# MCU_Design_exp.net
KiCad netlist of a schematic drawn in EAGLE
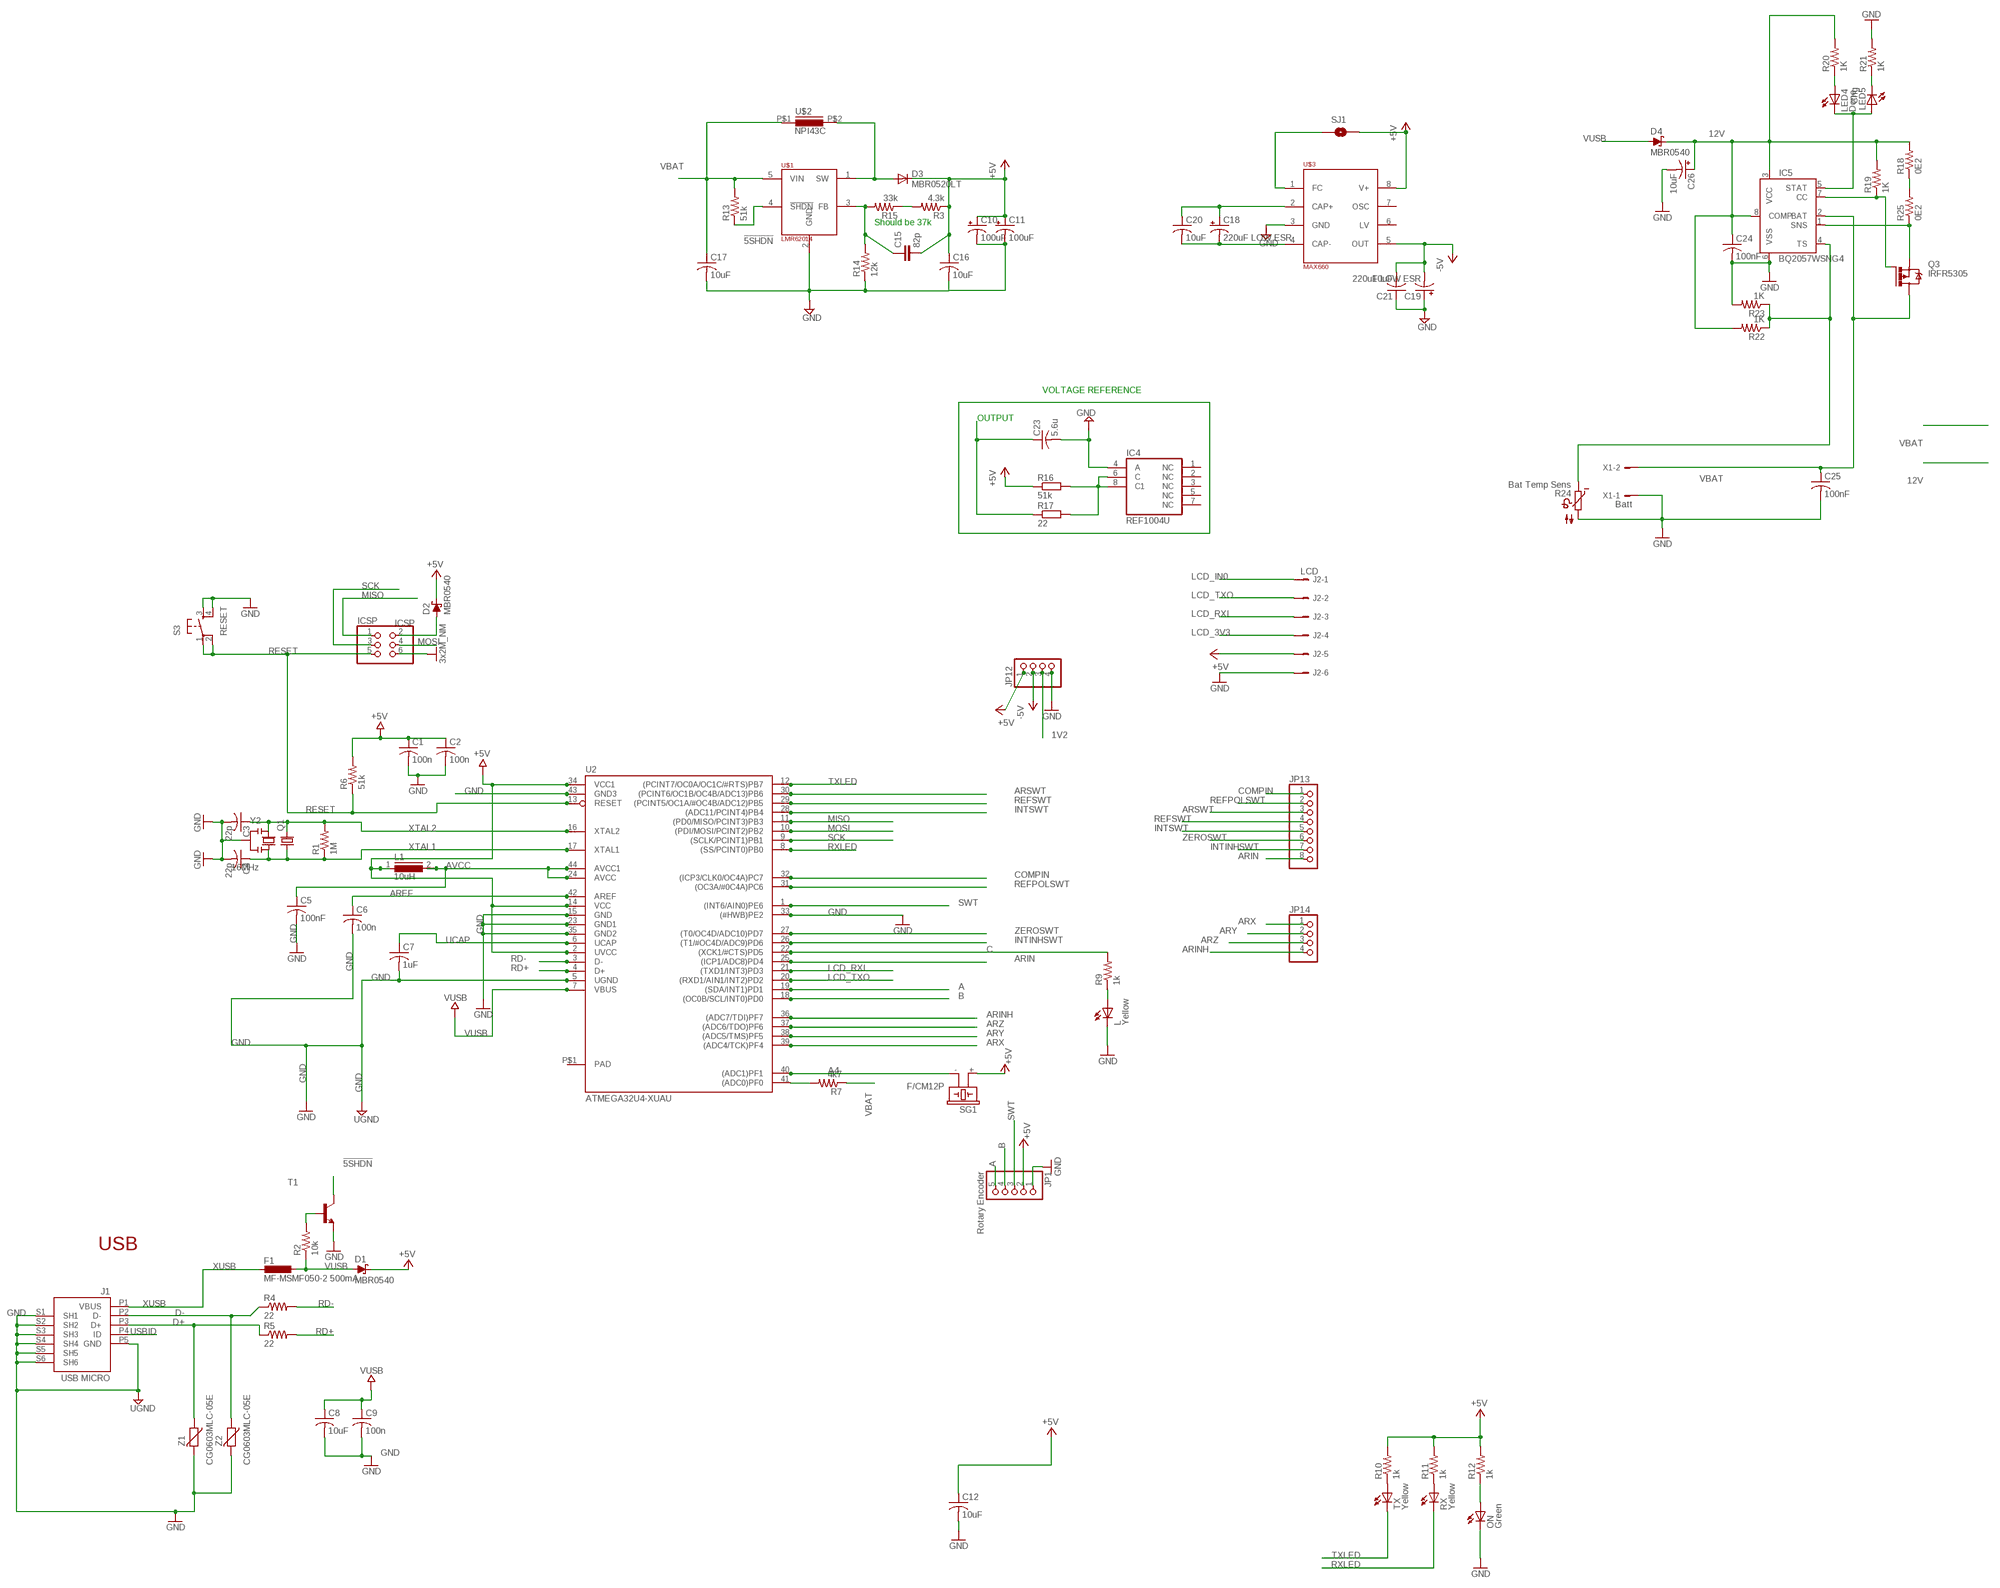
[diagram p0: schematic, sheet 1]

(export (version "E")
  (design (tool "Eeschema 10.0.6"))
  (components
    (comp (ref "C1")
      (value "100n")
      (footprint "eagle-import:C0805")
      (libsource (lib "eagle-import") (part "resistor_C-USC0805"))
    )
    (comp (ref "C2")
      (value "100n")
      (footprint "eagle-import:C0805")
      (libsource (lib "eagle-import") (part "resistor_C-USC0805"))
    )
    (comp (ref "C3")
      (value "22p")
      (footprint "eagle-import:C0805")
      (libsource (lib "eagle-import") (part "resistor_C-USC0805"))
    )
    (comp (ref "C4")
      (value "22p")
      (footprint "eagle-import:C0805")
      (libsource (lib "eagle-import") (part "resistor_C-USC0805"))
    )
    (comp (ref "C5")
      (value "100nF")
      (footprint "eagle-import:C0805")
      (libsource (lib "eagle-import") (part "resistor_C-USC0805"))
    )
    (comp (ref "C6")
      (value "100n")
      (footprint "eagle-import:C0805")
      (libsource (lib "eagle-import") (part "resistor_C-USC0805"))
    )
    (comp (ref "C7")
      (value "1uF")
      (footprint "eagle-import:C0805")
      (libsource (lib "eagle-import") (part "resistor_C-USC0805"))
    )
    (comp (ref "C8")
      (value "10uF")
      (footprint "eagle-import:C0805")
      (libsource (lib "eagle-import") (part "resistor_C-USC0805"))
    )
    (comp (ref "C9")
      (value "100n")
      (footprint "eagle-import:C0805")
      (libsource (lib "eagle-import") (part "resistor_C-USC0805"))
    )
    (comp (ref "C10")
      (value "100uF")
      (footprint "eagle-import:PANASONIC_D")
      (libsource (lib "eagle-import") (part "CPOL-USD"))
    )
    (comp (ref "C11")
      (value "100uF")
      (footprint "eagle-import:PANASONIC_D")
      (libsource (lib "eagle-import") (part "CPOL-USD"))
    )
    (comp (ref "C12")
      (value "10uF")
      (footprint "eagle-import:C0805")
      (libsource (lib "eagle-import") (part "resistor_C-USC0805"))
    )
    (comp (ref "C15")
      (value "82p")
      (footprint "eagle-import:C0805")
      (libsource (lib "eagle-import") (part "C-EUC0805"))
    )
    (comp (ref "C16")
      (value "10uF")
      (footprint "eagle-import:C0805")
      (libsource (lib "eagle-import") (part "resistor_C-USC0805"))
    )
    (comp (ref "C17")
      (value "10uF")
      (footprint "eagle-import:C0805")
      (libsource (lib "eagle-import") (part "resistor_C-USC0805"))
    )
    (comp (ref "C18")
      (value "220uF LOW ESR")
      (footprint "eagle-import:PANASONIC_D")
      (libsource (lib "eagle-import") (part "CPOL-USD"))
    )
    (comp (ref "C19")
      (value "220uF LOW ESR")
      (footprint "eagle-import:PANASONIC_D")
      (libsource (lib "eagle-import") (part "CPOL-USD"))
    )
    (comp (ref "C20")
      (value "10uF")
      (footprint "eagle-import:C0805")
      (libsource (lib "eagle-import") (part "resistor_C-USC0805"))
    )
    (comp (ref "C21")
      (value "10uF")
      (footprint "eagle-import:C0805")
      (libsource (lib "eagle-import") (part "resistor_C-USC0805"))
    )
    (comp (ref "C23")
      (value "5.6u")
      (footprint "eagle-import:C0805K")
      (libsource (lib "eagle-import") (part "C-USC0805K"))
    )
    (comp (ref "C24")
      (value "100nF")
      (footprint "eagle-import:C0805K")
      (libsource (lib "eagle-import") (part "resistor_C-USC0805K"))
    )
    (comp (ref "C25")
      (value "100nF")
      (footprint "eagle-import:C0805K")
      (libsource (lib "eagle-import") (part "resistor_C-USC0805K"))
    )
    (comp (ref "C26")
      (value "10uF")
      (footprint "eagle-import:153CLV-0405")
      (libsource (lib "eagle-import") (part "CPOL-US153CLV-0405"))
    )
    (comp (ref "D1")
      (value "MBR0540")
      (footprint "eagle-import:SOD123@2")
      (libsource (lib "eagle-import") (part "MBR0540"))
    )
    (comp (ref "D2")
      (value "MBR0540")
      (footprint "eagle-import:SOD123@2")
      (libsource (lib "eagle-import") (part "MBR0540"))
    )
    (comp (ref "D3")
      (value "MBR0520LT")
      (footprint "eagle-import:SOD123")
      (libsource (lib "eagle-import") (part "MBR0520LT"))
    )
    (comp (ref "D4")
      (value "MBR0540")
      (footprint "eagle-import:SOD123@2")
      (libsource (lib "eagle-import") (part "MBR0540"))
    )
    (comp (ref "F1")
      (value "MF-MSMF050-2 500mA")
      (footprint "eagle-import:L1812")
      (libsource (lib "eagle-import") (part "L-EUL1812"))
    )
    (comp (ref "IC4")
      (value "REF1004U")
      (footprint "eagle-import:SO08")
      (fields (field (name "MF") "TEXAS INSTRUMENTS") (field (name "MPN") "REF1004C-1.2"))
      (libsource (lib "eagle-import") (part "REF1004U"))
    )
    (comp (ref "IC5")
      (value "BQ2057WSNG4")
      (footprint "eagle-import:D_R-PDSO-G8")
      (libsource (lib "eagle-import") (part "BQ2057WSNG4"))
    )
    (comp (ref "ICSP")
      (value "ICSP")
      (footprint "eagle-import:2X03")
      (libsource (lib "eagle-import") (part "PINHD-2X3"))
    )
    (comp (ref "J1")
      (value "USB MICRO")
      (footprint "eagle-import:CON2_USB_MICRO_B_AT")
      (libsource (lib "eagle-import") (part "MYCON2_USB-MINI-B"))
    )
    (comp (ref "J2")
      (value "LCD")
      (footprint "eagle-import:7395-06")
      (libsource (lib "eagle-import") (part "22-?-0605-7068"))
    )
    (comp (ref "JP1")
      (value "Rotary Encoder")
      (footprint "eagle-import:1X05")
      (libsource (lib "eagle-import") (part "PINHD-1X5"))
    )
    (comp (ref "JP12")
      (value "PINHD-1X4")
      (footprint "eagle-import:1X04")
      (libsource (lib "eagle-import") (part "PINHD-1X4"))
    )
    (comp (ref "JP13")
      (value "PINHD-1X8")
      (footprint "eagle-import:1X08")
      (libsource (lib "eagle-import") (part "PINHD-1X8"))
    )
    (comp (ref "JP14")
      (value "PINHD-1X4")
      (footprint "eagle-import:1X04")
      (libsource (lib "eagle-import") (part "PINHD-1X4"))
    )
    (comp (ref "L")
      (value "Yellow")
      (footprint "eagle-import:CHIPLED_0805")
      (libsource (lib "eagle-import") (part "LEDCHIPLED_0805"))
    )
    (comp (ref "L1")
      (value "10uH")
      (footprint "eagle-import:MMICC7")
      (libsource (lib "eagle-import") (part "MMICC7"))
    )
    (comp (ref "LED4")
      (value "Done")
      (footprint "eagle-import:CHIPLED_0805")
      (libsource (lib "eagle-import") (part "LEDCHIPLED_0805"))
    )
    (comp (ref "LED5")
      (value "Chg")
      (footprint "eagle-import:CHIPLED_0805")
      (libsource (lib "eagle-import") (part "LEDCHIPLED_0805"))
    )
    (comp (ref "ON")
      (value "Green")
      (footprint "eagle-import:CHIPLED_0805")
      (libsource (lib "eagle-import") (part "LEDCHIPLED_0805"))
    )
    (comp (ref "Q1")
      (value "CRYSTALHC49UP")
      (footprint "eagle-import:HC49UP")
      (libsource (lib "eagle-import") (part "CRYSTALHC49UP"))
    )
    (comp (ref "Q3")
      (value "IRFR5305")
      (footprint "eagle-import:D-PAK_TO252AA")
      (libsource (lib "eagle-import") (part "IRF?5305R"))
    )
    (comp (ref "R1")
      (value "1M")
      (footprint "eagle-import:R0805")
      (libsource (lib "eagle-import") (part "R-US_R0805"))
    )
    (comp (ref "R2")
      (value "10k")
      (footprint "eagle-import:R0805")
      (libsource (lib "eagle-import") (part "R-US_R0805"))
    )
    (comp (ref "R3")
      (value "4.3k")
      (footprint "eagle-import:R0805")
      (libsource (lib "eagle-import") (part "R-US_R0805"))
    )
    (comp (ref "R4")
      (value "22")
      (footprint "eagle-import:R0805")
      (libsource (lib "eagle-import") (part "R-US_R0805"))
    )
    (comp (ref "R5")
      (value "22")
      (footprint "eagle-import:R0805")
      (libsource (lib "eagle-import") (part "R-US_R0805"))
    )
    (comp (ref "R6")
      (value "51k")
      (footprint "eagle-import:R0805")
      (libsource (lib "eagle-import") (part "R-US_R0805"))
    )
    (comp (ref "R7")
      (value "4k7")
      (footprint "eagle-import:R0805")
      (libsource (lib "eagle-import") (part "R-US_R0805"))
    )
    (comp (ref "R9")
      (value "1k")
      (footprint "eagle-import:R0805")
      (libsource (lib "eagle-import") (part "R-US_R0805"))
    )
    (comp (ref "R10")
      (value "1k")
      (footprint "eagle-import:R0805")
      (libsource (lib "eagle-import") (part "R-US_R0805"))
    )
    (comp (ref "R11")
      (value "1k")
      (footprint "eagle-import:R0805")
      (libsource (lib "eagle-import") (part "R-US_R0805"))
    )
    (comp (ref "R12")
      (value "1k")
      (footprint "eagle-import:R0805")
      (libsource (lib "eagle-import") (part "R-US_R0805"))
    )
    (comp (ref "R13")
      (value "51k")
      (footprint "eagle-import:R0805")
      (libsource (lib "eagle-import") (part "R-US_R0805"))
    )
    (comp (ref "R14")
      (value "12k")
      (footprint "eagle-import:R0805")
      (libsource (lib "eagle-import") (part "R-US_R0805"))
    )
    (comp (ref "R15")
      (value "33k")
      (footprint "eagle-import:R0805")
      (libsource (lib "eagle-import") (part "R-US_R0805"))
    )
    (comp (ref "R16")
      (value "51k")
      (footprint "eagle-import:M0805")
      (libsource (lib "eagle-import") (part "R-EU_M0805"))
    )
    (comp (ref "R17")
      (value "22")
      (footprint "eagle-import:M0805")
      (libsource (lib "eagle-import") (part "R-EU_M0805"))
    )
    (comp (ref "R18")
      (value "0E2")
      (footprint "eagle-import:M1206")
      (libsource (lib "eagle-import") (part "R-US_M1206"))
    )
    (comp (ref "R19")
      (value "1K")
      (footprint "eagle-import:R0805")
      (libsource (lib "eagle-import") (part "R-US_R0805"))
    )
    (comp (ref "R20")
      (value "1K")
      (footprint "eagle-import:R0805")
      (libsource (lib "eagle-import") (part "R-US_R0805"))
    )
    (comp (ref "R21")
      (value "1K")
      (footprint "eagle-import:R0805")
      (libsource (lib "eagle-import") (part "R-US_R0805"))
    )
    (comp (ref "R22")
      (value "1K")
      (footprint "eagle-import:R0805")
      (libsource (lib "eagle-import") (part "R-US_R0805"))
    )
    (comp (ref "R23")
      (value "1K")
      (footprint "eagle-import:R0805")
      (libsource (lib "eagle-import") (part "R-US_R0805"))
    )
    (comp (ref "R24")
      (value "Bat Temp Sens")
      (footprint "eagle-import:P640")
      (libsource (lib "eagle-import") (part "NTC640"))
    )
    (comp (ref "R25")
      (value "0E2")
      (footprint "eagle-import:M1206")
      (libsource (lib "eagle-import") (part "R-US_M1206"))
    )
    (comp (ref "RX")
      (value "Yellow")
      (footprint "eagle-import:CHIPLED_0805")
      (libsource (lib "eagle-import") (part "LEDCHIPLED_0805"))
    )
    (comp (ref "S3")
      (value "RESET")
      (footprint "eagle-import:TACTILE_SWITCH_SMD")
      (libsource (lib "eagle-import") (part "TAC_SWITCHSMD"))
    )
    (comp (ref "SG1")
      (value "F/CM12P")
      (footprint "eagle-import:F_CM12P")
      (libsource (lib "eagle-import") (part "F/CM12P"))
    )
    (comp (ref "SJ1")
      (value "SOLDERJUMPERTRACE")
      (footprint "eagle-import:SJ_2S-TRACE")
      (libsource (lib "eagle-import") (part "SOLDERJUMPERTRACE"))
    )
    (comp (ref "T1")
      (value "MMBT2222ALT1-NPN-SOT23-BEC")
      (footprint "eagle-import:SOT23-BEC")
      (libsource (lib "eagle-import") (part "-NPN-SOT23-BECMMBT2222ALT1"))
    )
    (comp (ref "TX")
      (value "Yellow")
      (footprint "eagle-import:CHIPLED_0805")
      (libsource (lib "eagle-import") (part "LEDCHIPLED_0805"))
    )
    (comp (ref "U$1")
      (value "LMR62014")
      (footprint "eagle-import:SOT23-5")
      (libsource (lib "eagle-import") (part "LMR62014"))
    )
    (comp (ref "U$2")
      (value "NPI43C")
      (footprint "eagle-import:NPI43C")
      (libsource (lib "eagle-import") (part "NPI43C"))
    )
    (comp (ref "U$3")
      (value "MAX660")
      (footprint "eagle-import:SO08")
      (libsource (lib "eagle-import") (part "MAX660"))
    )
    (comp (ref "U2")
      (value "ATMEGA32U4-XUAU")
      (footprint "eagle-import:TQFP44-PAD")
      (libsource (lib "eagle-import") (part "ATMEGA32U4-XUAU"))
    )
    (comp (ref "X1")
      (value "Batt")
      (footprint "eagle-import:22-23-2021")
      (fields (field (name "MF") "MOLEX") (field (name "MPN") "22-23-2021"))
      (libsource (lib "eagle-import") (part "22-23-2021"))
    )
    (comp (ref "Y2")
      (value "16MHz")
      (footprint "eagle-import:RESONATOR")
      (libsource (lib "eagle-import") (part "RESONATORMU"))
    )
    (comp (ref "Z1")
      (value "CG0603MLC-05E")
      (footprint "eagle-import:CT_CN0603")
      (libsource (lib "eagle-import") (part "VARISTORCN0603"))
    )
    (comp (ref "Z2")
      (value "CG0603MLC-05E")
      (footprint "eagle-import:CT_CN0603")
      (libsource (lib "eagle-import") (part "VARISTORCN0603"))
    )
  )
  (nets
    (net (code "1") (name "+5V") (class "Default")
      (node (ref "C1") (pin "1") (pinfunction "1_1") (pintype "passive"))
      (node (ref "C10") (pin "+") (pinfunction "+_+") (pintype "passive"))
      (node (ref "C11") (pin "+") (pinfunction "+_+") (pintype "passive"))
      (node (ref "C12") (pin "1") (pinfunction "1_1") (pintype "passive"))
      (node (ref "C15") (pin "2") (pinfunction "2_2") (pintype "passive"))
      (node (ref "C16") (pin "1") (pinfunction "1_1") (pintype "passive"))
      (node (ref "C2") (pin "1") (pinfunction "1_1") (pintype "passive"))
      (node (ref "D1") (pin "C") (pinfunction "C_C") (pintype "passive"))
      (node (ref "D2") (pin "C") (pinfunction "C_C") (pintype "passive"))
      (node (ref "D3") (pin "C") (pinfunction "C_C") (pintype "passive"))
      (node (ref "J2") (pin "5") (pinfunction "S_5") (pintype "passive"))
      (node (ref "JP1") (pin "2") (pinfunction "2_2") (pintype "passive"))
      (node (ref "JP12") (pin "1") (pinfunction "1_1") (pintype "passive"))
      (node (ref "L1") (pin "1") (pinfunction "1_1") (pintype "passive"))
      (node (ref "R10") (pin "2") (pinfunction "2_2") (pintype "passive"))
      (node (ref "R11") (pin "2") (pinfunction "2_2") (pintype "passive"))
      (node (ref "R12") (pin "2") (pinfunction "2_2") (pintype "passive"))
      (node (ref "R16") (pin "1") (pinfunction "1_1") (pintype "passive"))
      (node (ref "R3") (pin "1") (pinfunction "1_1") (pintype "passive"))
      (node (ref "R6") (pin "2") (pinfunction "2_2") (pintype "passive"))
      (node (ref "SG1") (pin "+") (pinfunction "1_+") (pintype "passive"))
      (node (ref "SJ1") (pin "2") (pinfunction "2_2") (pintype "passive"))
      (node (ref "U$3") (pin "8") (pinfunction "V+_8") (pintype "bidirectional"))
      (node (ref "U2") (pin "14") (pinfunction "VCC_14") (pintype "power_in"))
      (node (ref "U2") (pin "2") (pinfunction "UVCC_2") (pintype "power_in"))
      (node (ref "U2") (pin "34") (pinfunction "VCC1_34") (pintype "power_in"))
    )
    (net (code "2") (name "-5V") (class "Default")
      (node (ref "C19") (pin "-") (pinfunction "-_-") (pintype "passive"))
      (node (ref "C21") (pin "2") (pinfunction "2_2") (pintype "passive"))
      (node (ref "JP12") (pin "2") (pinfunction "2_2") (pintype "passive"))
      (node (ref "U$3") (pin "5") (pinfunction "OUT_5") (pintype "bidirectional"))
    )
    (net (code "3") (name "/1V2") (class "Default")
      (node (ref "C23") (pin "1") (pinfunction "1_1") (pintype "passive"))
      (node (ref "JP12") (pin "3") (pinfunction "3_3") (pintype "passive"))
      (node (ref "R17") (pin "1") (pinfunction "1_1") (pintype "passive"))
    )
    (net (code "4") (name "/12V") (class "Default")
      (node (ref "C24") (pin "1") (pinfunction "1_1") (pintype "passive"))
      (node (ref "C26") (pin "+") (pinfunction "+_+") (pintype "passive"))
      (node (ref "D4") (pin "C") (pinfunction "C_C") (pintype "passive"))
      (node (ref "IC5") (pin "3") (pinfunction "VCC_3") (pintype "input"))
      (node (ref "IC5") (pin "8") (pinfunction "COMP_8") (pintype "input"))
      (node (ref "R18") (pin "2") (pinfunction "2_2") (pintype "passive"))
      (node (ref "R19") (pin "2") (pinfunction "2_2") (pintype "passive"))
      (node (ref "R20") (pin "2") (pinfunction "2_2") (pintype "passive"))
      (node (ref "R22") (pin "2") (pinfunction "2_2") (pintype "passive"))
    )
    (net (code "5") (name "/A") (class "Default")
      (node (ref "JP1") (pin "5") (pinfunction "5_5") (pintype "passive"))
      (node (ref "U2") (pin "19") (pinfunction "(SDA/INT1)PD1_19") (pintype "bidirectional"))
    )
    (net (code "6") (name "/A4") (class "Default")
      (node (ref "SG1") (pin "-") (pinfunction "2_-") (pintype "passive"))
      (node (ref "U2") (pin "40") (pinfunction "(ADC1)PF1_40") (pintype "bidirectional"))
    )
    (net (code "7") (name "/AREF") (class "Default")
      (node (ref "C6") (pin "1") (pinfunction "1_1") (pintype "passive"))
      (node (ref "U2") (pin "42") (pinfunction "AREF_42") (pintype "power_in"))
    )
    (net (code "8") (name "/ARIN") (class "Default")
      (node (ref "JP13") (pin "8") (pinfunction "8_8") (pintype "passive"))
      (node (ref "U2") (pin "25") (pinfunction "(ICP1/ADC8)PD4_25") (pintype "bidirectional"))
    )
    (net (code "9") (name "/ARINH") (class "Default")
      (node (ref "JP14") (pin "4") (pinfunction "4_4") (pintype "passive"))
      (node (ref "U2") (pin "36") (pinfunction "(ADC7/TDI)PF7_36") (pintype "bidirectional"))
    )
    (net (code "10") (name "/ARSWT") (class "Default")
      (node (ref "JP13") (pin "3") (pinfunction "3_3") (pintype "passive"))
      (node (ref "U2") (pin "30") (pinfunction "(PCINT6/OC1B/OC4B/ADC13)PB6_30") (pintype "bidirectional"))
    )
    (net (code "11") (name "/ARX") (class "Default")
      (node (ref "JP14") (pin "1") (pinfunction "1_1") (pintype "passive"))
      (node (ref "U2") (pin "39") (pinfunction "(ADC4/TCK)PF4_39") (pintype "bidirectional"))
    )
    (net (code "12") (name "/ARY") (class "Default")
      (node (ref "JP14") (pin "2") (pinfunction "2_2") (pintype "passive"))
      (node (ref "U2") (pin "38") (pinfunction "(ADC5/TMS)PF5_38") (pintype "bidirectional"))
    )
    (net (code "13") (name "/ARZ") (class "Default")
      (node (ref "JP14") (pin "3") (pinfunction "3_3") (pintype "passive"))
      (node (ref "U2") (pin "37") (pinfunction "(ADC6/TDO)PF6_37") (pintype "bidirectional"))
    )
    (net (code "14") (name "/AVCC") (class "Default")
      (node (ref "C5") (pin "1") (pinfunction "1_1") (pintype "passive"))
      (node (ref "L1") (pin "2") (pinfunction "2_2") (pintype "passive"))
      (node (ref "U2") (pin "24") (pinfunction "AVCC_24") (pintype "power_in"))
      (node (ref "U2") (pin "44") (pinfunction "AVCC1_44") (pintype "power_in"))
    )
    (net (code "15") (name "/B") (class "Default")
      (node (ref "JP1") (pin "4") (pinfunction "4_4") (pintype "passive"))
      (node (ref "U2") (pin "18") (pinfunction "(OC0B/SCL/INT0)PD0_18") (pintype "bidirectional"))
    )
    (net (code "16") (name "/C") (class "Default")
      (node (ref "R9") (pin "2") (pinfunction "2_2") (pintype "passive"))
      (node (ref "U2") (pin "22") (pinfunction "(XCK1/#CTS)PD5_22") (pintype "bidirectional"))
    )
    (net (code "17") (name "/COMPIN") (class "Default")
      (node (ref "JP13") (pin "1") (pinfunction "1_1") (pintype "passive"))
      (node (ref "U2") (pin "32") (pinfunction "(ICP3/CLK0/OC4A)PC7_32") (pintype "bidirectional"))
    )
    (net (code "18") (name "/D+") (class "Default")
      (node (ref "J1") (pin "P3") (pinfunction "D+_P3") (pintype "bidirectional"))
      (node (ref "R5") (pin "1") (pinfunction "1_1") (pintype "passive"))
      (node (ref "Z1") (pin "1") (pinfunction "1_1") (pintype "passive"))
    )
    (net (code "19") (name "/D-") (class "Default")
      (node (ref "J1") (pin "P2") (pinfunction "D-_P2") (pintype "bidirectional"))
      (node (ref "R4") (pin "1") (pinfunction "1_1") (pintype "passive"))
      (node (ref "Z2") (pin "1") (pinfunction "1_1") (pintype "passive"))
    )
    (net (code "20") (name "/INTINHSWT") (class "Default")
      (node (ref "JP13") (pin "7") (pinfunction "7_7") (pintype "passive"))
      (node (ref "U2") (pin "26") (pinfunction "(T1/#OC4D/ADC9)PD6_26") (pintype "bidirectional"))
    )
    (net (code "21") (name "/INTSWT") (class "Default")
      (node (ref "JP13") (pin "5") (pinfunction "5_5") (pintype "passive"))
      (node (ref "U2") (pin "28") (pinfunction "(ADC11/PCINT4)PB4_28") (pintype "bidirectional"))
    )
    (net (code "22") (name "/LCD_3V3") (class "Default")
      (node (ref "J2") (pin "4") (pinfunction "S_4") (pintype "passive"))
    )
    (net (code "23") (name "/LCD_IN0") (class "Default")
      (node (ref "J2") (pin "1") (pinfunction "S_1") (pintype "passive"))
    )
    (net (code "24") (name "/LCD_RXI") (class "Default")
      (node (ref "J2") (pin "3") (pinfunction "S_3") (pintype "passive"))
      (node (ref "U2") (pin "21") (pinfunction "(TXD1/INT3)PD3_21") (pintype "bidirectional"))
    )
    (net (code "25") (name "/LCD_TXO") (class "Default")
      (node (ref "J2") (pin "2") (pinfunction "S_2") (pintype "passive"))
      (node (ref "U2") (pin "20") (pinfunction "(RXD1/AIN1/INT2)PD2_20") (pintype "bidirectional"))
    )
    (net (code "26") (name "/MISO") (class "Default")
      (node (ref "ICSP") (pin "1") (pinfunction "1_1") (pintype "passive"))
      (node (ref "U2") (pin "11") (pinfunction "(PD0/MISO/PCINT3)PB3_11") (pintype "bidirectional"))
    )
    (net (code "27") (name "/MOSI") (class "Default")
      (node (ref "ICSP") (pin "4") (pinfunction "4_4") (pintype "passive"))
      (node (ref "U2") (pin "10") (pinfunction "(PDI/MOSI/PCINT2)PB2_10") (pintype "bidirectional"))
    )
    (net (code "28") (name "/PAD") (class "Default")
      (node (ref "U2") (pin "P$1") (pinfunction "PAD_P$1") (pintype "power_in"))
    )
    (net (code "29") (name "/RD+") (class "Default")
      (node (ref "R5") (pin "2") (pinfunction "2_2") (pintype "passive"))
      (node (ref "U2") (pin "4") (pinfunction "D+_4") (pintype "bidirectional"))
    )
    (net (code "30") (name "/RD-") (class "Default")
      (node (ref "R4") (pin "2") (pinfunction "2_2") (pintype "passive"))
      (node (ref "U2") (pin "3") (pinfunction "D-_3") (pintype "bidirectional"))
    )
    (net (code "31") (name "/REFPOLSWT") (class "Default")
      (node (ref "JP13") (pin "2") (pinfunction "2_2") (pintype "passive"))
      (node (ref "U2") (pin "31") (pinfunction "(OC3A/#0C4A)PC6_31") (pintype "bidirectional"))
    )
    (net (code "32") (name "/REFSWT") (class "Default")
      (node (ref "JP13") (pin "4") (pinfunction "4_4") (pintype "passive"))
      (node (ref "U2") (pin "29") (pinfunction "(PCINT5/OC1A/#OC4B/ADC12)PB5_29") (pintype "bidirectional"))
    )
    (net (code "33") (name "/RESET") (class "Default")
      (node (ref "ICSP") (pin "5") (pinfunction "5_5") (pintype "passive"))
      (node (ref "R6") (pin "1") (pinfunction "1_1") (pintype "passive"))
      (node (ref "S3") (pin "1") (pinfunction "1_1") (pintype "passive"))
      (node (ref "S3") (pin "2") (pinfunction "2_2") (pintype "passive"))
      (node (ref "U2") (pin "13") (pinfunction "RESET_13") (pintype "input"))
    )
    (net (code "34") (name "/RXLED") (class "Default")
      (node (ref "RX") (pin "C") (pinfunction "C_C") (pintype "passive"))
      (node (ref "U2") (pin "8") (pinfunction "(SS/PCINT0)PB0_8") (pintype "bidirectional"))
    )
    (net (code "35") (name "/SCK") (class "Default")
      (node (ref "ICSP") (pin "3") (pinfunction "3_3") (pintype "passive"))
      (node (ref "U2") (pin "9") (pinfunction "(SCLK/PCINT1)PB1_9") (pintype "bidirectional"))
    )
    (net (code "36") (name "/SWT") (class "Default")
      (node (ref "JP1") (pin "3") (pinfunction "3_3") (pintype "passive"))
      (node (ref "U2") (pin "1") (pinfunction "(INT6/AIN0)PE6_1") (pintype "bidirectional"))
    )
    (net (code "37") (name "/TXLED") (class "Default")
      (node (ref "TX") (pin "C") (pinfunction "C_C") (pintype "passive"))
      (node (ref "U2") (pin "12") (pinfunction "(PCINT7/OC0A/OC1C/#RTS)PB7_12") (pintype "bidirectional"))
    )
    (net (code "38") (name "/UCAP") (class "Default")
      (node (ref "C7") (pin "1") (pinfunction "1_1") (pintype "passive"))
      (node (ref "U2") (pin "6") (pinfunction "UCAP_6") (pintype "passive"))
    )
    (net (code "39") (name "/USBID") (class "Default")
      (node (ref "J1") (pin "P4") (pinfunction "ID_P4") (pintype "bidirectional"))
    )
    (net (code "40") (name "/VBAT") (class "Default")
      (node (ref "C17") (pin "1") (pinfunction "1_1") (pintype "passive"))
      (node (ref "C25") (pin "1") (pinfunction "1_1") (pintype "passive"))
      (node (ref "IC5") (pin "2") (pinfunction "BAT_2") (pintype "input"))
      (node (ref "Q3") (pin "4") (pinfunction "D_4") (pintype "passive"))
      (node (ref "R13") (pin "2") (pinfunction "2_2") (pintype "passive"))
      (node (ref "R7") (pin "1") (pinfunction "1_1") (pintype "passive"))
      (node (ref "U$1") (pin "5") (pinfunction "VIN_5") (pintype "bidirectional"))
      (node (ref "U$2") (pin "P$1") (pinfunction "1_P$1") (pintype "passive"))
      (node (ref "X1") (pin "2") (pinfunction "S_2") (pintype "passive"))
    )
    (net (code "41") (name "/XTAL1") (class "Default")
      (node (ref "C4") (pin "1") (pinfunction "1_1") (pintype "passive"))
      (node (ref "Q1") (pin "1") (pinfunction "1_1") (pintype "passive"))
      (node (ref "R1") (pin "1") (pinfunction "1_1") (pintype "passive"))
      (node (ref "U2") (pin "17") (pinfunction "XTAL1_17") (pintype "bidirectional"))
      (node (ref "Y2") (pin "3") (pinfunction "3_3") (pintype "passive"))
    )
    (net (code "42") (name "/XTAL2") (class "Default")
      (node (ref "C3") (pin "1") (pinfunction "1_1") (pintype "passive"))
      (node (ref "Q1") (pin "2") (pinfunction "2_2") (pintype "passive"))
      (node (ref "R1") (pin "2") (pinfunction "2_2") (pintype "passive"))
      (node (ref "U2") (pin "16") (pinfunction "XTAL2_16") (pintype "bidirectional"))
      (node (ref "Y2") (pin "1") (pinfunction "1_1") (pintype "passive"))
    )
    (net (code "43") (name "/XUSB") (class "Default")
      (node (ref "F1") (pin "2") (pinfunction "2_2") (pintype "passive"))
      (node (ref "J1") (pin "P1") (pinfunction "VBUS_P1") (pintype "power_in"))
    )
    (net (code "44") (name "/ZEROSWT") (class "Default")
      (node (ref "JP13") (pin "6") (pinfunction "6_6") (pintype "passive"))
      (node (ref "U2") (pin "27") (pinfunction "(T0/OC4D/ADC10)PD7_27") (pintype "bidirectional"))
    )
    (net (code "45") (name "/~{5SHDN}") (class "Default")
      (node (ref "R13") (pin "1") (pinfunction "1_1") (pintype "passive"))
      (node (ref "T1") (pin "C") (pinfunction "C_C") (pintype "passive"))
      (node (ref "U$1") (pin "4") (pinfunction "~{SHDN}_4") (pintype "bidirectional"))
    )
    (net (code "46") (name "3x2M_NM") (class "Default")
      (node (ref "C1") (pin "2") (pinfunction "2_2") (pintype "passive"))
      (node (ref "C10") (pin "-") (pinfunction "-_-") (pintype "passive"))
      (node (ref "C11") (pin "-") (pinfunction "-_-") (pintype "passive"))
      (node (ref "C12") (pin "2") (pinfunction "2_2") (pintype "passive"))
      (node (ref "C16") (pin "2") (pinfunction "2_2") (pintype "passive"))
      (node (ref "C17") (pin "2") (pinfunction "2_2") (pintype "passive"))
      (node (ref "C19") (pin "+") (pinfunction "+_+") (pintype "passive"))
      (node (ref "C2") (pin "2") (pinfunction "2_2") (pintype "passive"))
      (node (ref "C21") (pin "1") (pinfunction "1_1") (pintype "passive"))
      (node (ref "C23") (pin "2") (pinfunction "2_2") (pintype "passive"))
      (node (ref "C24") (pin "2") (pinfunction "2_2") (pintype "passive"))
      (node (ref "C25") (pin "2") (pinfunction "2_2") (pintype "passive"))
      (node (ref "C26") (pin "-") (pinfunction "-_-") (pintype "passive"))
      (node (ref "C3") (pin "2") (pinfunction "2_2") (pintype "passive"))
      (node (ref "C4") (pin "2") (pinfunction "2_2") (pintype "passive"))
      (node (ref "C5") (pin "2") (pinfunction "2_2") (pintype "passive"))
      (node (ref "C6") (pin "2") (pinfunction "2_2") (pintype "passive"))
      (node (ref "C7") (pin "2") (pinfunction "2_2") (pintype "passive"))
      (node (ref "C8") (pin "2") (pinfunction "2_2") (pintype "passive"))
      (node (ref "C9") (pin "2") (pinfunction "2_2") (pintype "passive"))
      (node (ref "IC4") (pin "4") (pinfunction "A_4") (pintype "passive"))
      (node (ref "IC5") (pin "6") (pinfunction "VSS_6") (pintype "power_in"))
      (node (ref "ICSP") (pin "6") (pinfunction "6_6") (pintype "passive"))
      (node (ref "J1") (pin "P5") (pinfunction "GND_P5") (pintype "passive"))
      (node (ref "J1") (pin "S1") (pinfunction "SH1_S1") (pintype "passive"))
      (node (ref "J1") (pin "S2") (pinfunction "SH2_S2") (pintype "passive"))
      (node (ref "J1") (pin "S3") (pinfunction "SH3_S3") (pintype "passive"))
      (node (ref "J1") (pin "S4") (pinfunction "SH4_S4") (pintype "passive"))
      (node (ref "J1") (pin "S5") (pinfunction "SH5_S5") (pintype "passive"))
      (node (ref "J1") (pin "S6") (pinfunction "SH6_S6") (pintype "passive"))
      (node (ref "J2") (pin "6") (pinfunction "S_6") (pintype "passive"))
      (node (ref "JP1") (pin "1") (pinfunction "1_1") (pintype "passive"))
      (node (ref "JP12") (pin "4") (pinfunction "4_4") (pintype "passive"))
      (node (ref "L") (pin "C") (pinfunction "C_C") (pintype "passive"))
      (node (ref "ON") (pin "C") (pinfunction "C_C") (pintype "passive"))
      (node (ref "R14") (pin "1") (pinfunction "1_1") (pintype "passive"))
      (node (ref "R21") (pin "2") (pinfunction "2_2") (pintype "passive"))
      (node (ref "R23") (pin "2") (pinfunction "2_2") (pintype "passive"))
      (node (ref "R24") (pin "2") (pinfunction "2_2") (pintype "passive"))
      (node (ref "S3") (pin "3") (pinfunction "3_3") (pintype "passive"))
      (node (ref "S3") (pin "4") (pinfunction "4_4") (pintype "passive"))
      (node (ref "T1") (pin "E") (pinfunction "E_E") (pintype "passive"))
      (node (ref "U$1") (pin "2") (pinfunction "GND_2") (pintype "bidirectional"))
      (node (ref "U$3") (pin "3") (pinfunction "GND_3") (pintype "bidirectional"))
      (node (ref "U2") (pin "15") (pinfunction "GND_15") (pintype "power_in"))
      (node (ref "U2") (pin "23") (pinfunction "GND1_23") (pintype "power_in"))
      (node (ref "U2") (pin "33") (pinfunction "(#HWB)PE2_33") (pintype "bidirectional"))
      (node (ref "U2") (pin "35") (pinfunction "GND2_35") (pintype "power_in"))
      (node (ref "U2") (pin "43") (pinfunction "GND3_43") (pintype "power_in"))
      (node (ref "U2") (pin "5") (pinfunction "UGND_5") (pintype "power_in"))
      (node (ref "X1") (pin "1") (pinfunction "S_1") (pintype "passive"))
      (node (ref "Y2") (pin "2") (pinfunction "2_2") (pintype "passive"))
      (node (ref "Z1") (pin "2") (pinfunction "2_2") (pintype "passive"))
      (node (ref "Z2") (pin "2") (pinfunction "2_2") (pintype "passive"))
    )
    (net (code "47") (name "Net-(D2-PadA)") (class "Default")
      (node (ref "D2") (pin "A") (pinfunction "A_A") (pintype "passive"))
      (node (ref "ICSP") (pin "2") (pinfunction "2_2") (pintype "passive"))
    )
    (net (code "48") (name "Net-(IC4-C)") (class "Default")
      (node (ref "IC4") (pin "6") (pinfunction "C_6") (pintype "passive"))
      (node (ref "IC4") (pin "8") (pinfunction "C1_8") (pintype "passive"))
      (node (ref "R16") (pin "2") (pinfunction "2_2") (pintype "passive"))
      (node (ref "R17") (pin "2") (pinfunction "2_2") (pintype "passive"))
    )
    (net (code "49") (name "Net-(IC5-CC)") (class "Default")
      (node (ref "IC5") (pin "7") (pinfunction "CC_7") (pintype "output"))
      (node (ref "Q3") (pin "1") (pinfunction "G_1") (pintype "passive"))
      (node (ref "R19") (pin "1") (pinfunction "1_1") (pintype "passive"))
    )
    (net (code "50") (name "Net-(IC5-SNS)") (class "Default")
      (node (ref "IC5") (pin "1") (pinfunction "SNS_1") (pintype "input"))
      (node (ref "Q3") (pin "3") (pinfunction "S_3") (pintype "passive"))
      (node (ref "R25") (pin "1") (pinfunction "1_1") (pintype "passive"))
    )
    (net (code "51") (name "Net-(IC5-STAT)") (class "Default")
      (node (ref "IC5") (pin "5") (pinfunction "STAT_5") (pintype "output"))
      (node (ref "LED4") (pin "C") (pinfunction "C_C") (pintype "passive"))
      (node (ref "LED5") (pin "A") (pinfunction "A_A") (pintype "passive"))
    )
    (net (code "52") (name "Net-(IC5-TS)") (class "Default")
      (node (ref "IC5") (pin "4") (pinfunction "TS_4") (pintype "input"))
      (node (ref "R22") (pin "1") (pinfunction "1_1") (pintype "passive"))
      (node (ref "R23") (pin "1") (pinfunction "1_1") (pintype "passive"))
      (node (ref "R24") (pin "1") (pinfunction "1_1") (pintype "passive"))
    )
    (net (code "53") (name "Net-(L-PadA)") (class "Default")
      (node (ref "L") (pin "A") (pinfunction "A_A") (pintype "passive"))
      (node (ref "R9") (pin "1") (pinfunction "1_1") (pintype "passive"))
    )
    (net (code "54") (name "Net-(LED4-PadA)") (class "Default")
      (node (ref "LED4") (pin "A") (pinfunction "A_A") (pintype "passive"))
      (node (ref "R20") (pin "1") (pinfunction "1_1") (pintype "passive"))
    )
    (net (code "55") (name "Net-(LED5-PadC)") (class "Default")
      (node (ref "LED5") (pin "C") (pinfunction "C_C") (pintype "passive"))
      (node (ref "R21") (pin "1") (pinfunction "1_1") (pintype "passive"))
    )
    (net (code "56") (name "Net-(ON-PadA)") (class "Default")
      (node (ref "ON") (pin "A") (pinfunction "A_A") (pintype "passive"))
      (node (ref "R12") (pin "1") (pinfunction "1_1") (pintype "passive"))
    )
    (net (code "57") (name "Net-(R2-Pad2)") (class "Default")
      (node (ref "R2") (pin "2") (pinfunction "2_2") (pintype "passive"))
      (node (ref "T1") (pin "B") (pinfunction "B_B") (pintype "passive"))
    )
    (net (code "58") (name "Net-(R10-Pad1)") (class "Default")
      (node (ref "R10") (pin "1") (pinfunction "1_1") (pintype "passive"))
      (node (ref "TX") (pin "A") (pinfunction "A_A") (pintype "passive"))
    )
    (net (code "59") (name "Net-(R11-Pad1)") (class "Default")
      (node (ref "R11") (pin "1") (pinfunction "1_1") (pintype "passive"))
      (node (ref "RX") (pin "A") (pinfunction "A_A") (pintype "passive"))
    )
    (net (code "60") (name "Net-(R15-Pad1)") (class "Default")
      (node (ref "R15") (pin "1") (pinfunction "1_1") (pintype "passive"))
      (node (ref "R3") (pin "2") (pinfunction "2_2") (pintype "passive"))
    )
    (net (code "61") (name "Net-(R18-Pad1)") (class "Default")
      (node (ref "R18") (pin "1") (pinfunction "1_1") (pintype "passive"))
      (node (ref "R25") (pin "2") (pinfunction "2_2") (pintype "passive"))
    )
    (net (code "62") (name "Net-(U$1-FB)") (class "Default")
      (node (ref "C15") (pin "1") (pinfunction "1_1") (pintype "passive"))
      (node (ref "R14") (pin "2") (pinfunction "2_2") (pintype "passive"))
      (node (ref "R15") (pin "2") (pinfunction "2_2") (pintype "passive"))
      (node (ref "U$1") (pin "3") (pinfunction "FB_3") (pintype "bidirectional"))
    )
    (net (code "63") (name "Net-(U$1-SW)") (class "Default")
      (node (ref "D3") (pin "A") (pinfunction "A_A") (pintype "passive"))
      (node (ref "U$1") (pin "1") (pinfunction "SW_1") (pintype "bidirectional"))
      (node (ref "U$2") (pin "P$2") (pinfunction "2_P$2") (pintype "passive"))
    )
    (net (code "64") (name "Net-(U$3-CAP+)") (class "Default")
      (node (ref "C18") (pin "+") (pinfunction "+_+") (pintype "passive"))
      (node (ref "C20") (pin "1") (pinfunction "1_1") (pintype "passive"))
      (node (ref "U$3") (pin "2") (pinfunction "CAP+_2") (pintype "bidirectional"))
    )
    (net (code "65") (name "Net-(U$3-CAP-)") (class "Default")
      (node (ref "C18") (pin "-") (pinfunction "-_-") (pintype "passive"))
      (node (ref "C20") (pin "2") (pinfunction "2_2") (pintype "passive"))
      (node (ref "U$3") (pin "4") (pinfunction "CAP-_4") (pintype "bidirectional"))
    )
    (net (code "66") (name "Net-(U$3-FC)") (class "Default")
      (node (ref "SJ1") (pin "1") (pinfunction "1_1") (pintype "passive"))
      (node (ref "U$3") (pin "1") (pinfunction "FC_1") (pintype "bidirectional"))
    )
    (net (code "67") (name "Net-(U2-(ADC0)PF0)") (class "Default")
      (node (ref "R7") (pin "2") (pinfunction "2_2") (pintype "passive"))
      (node (ref "U2") (pin "41") (pinfunction "(ADC0)PF0_41") (pintype "bidirectional"))
    )
    (net (code "68") (name "VUSB") (class "Default")
      (node (ref "C8") (pin "1") (pinfunction "1_1") (pintype "passive"))
      (node (ref "C9") (pin "1") (pinfunction "1_1") (pintype "passive"))
      (node (ref "D1") (pin "A") (pinfunction "A_A") (pintype "passive"))
      (node (ref "D4") (pin "A") (pinfunction "A_A") (pintype "passive"))
      (node (ref "F1") (pin "1") (pinfunction "1_1") (pintype "passive"))
      (node (ref "R2") (pin "1") (pinfunction "1_1") (pintype "passive"))
      (node (ref "U2") (pin "7") (pinfunction "VBUS_7") (pintype "input"))
    )
    (net (code "69") (name "unconnected-(IC4-NC-Pad1)") (class "Default")
      (node (ref "IC4") (pin "1") (pinfunction "NC_1") (pintype "no_connect"))
    )
    (net (code "70") (name "unconnected-(IC4-NC-Pad2)") (class "Default")
      (node (ref "IC4") (pin "2") (pinfunction "NC_2") (pintype "no_connect"))
    )
    (net (code "71") (name "unconnected-(IC4-NC-Pad3)") (class "Default")
      (node (ref "IC4") (pin "3") (pinfunction "NC_3") (pintype "no_connect"))
    )
    (net (code "72") (name "unconnected-(IC4-NC-Pad5)") (class "Default")
      (node (ref "IC4") (pin "5") (pinfunction "NC_5") (pintype "no_connect"))
    )
    (net (code "73") (name "unconnected-(IC4-NC-Pad7)") (class "Default")
      (node (ref "IC4") (pin "7") (pinfunction "NC_7") (pintype "no_connect"))
    )
    (net (code "74") (name "unconnected-(U$3-LV-Pad6)") (class "Default")
      (node (ref "U$3") (pin "6") (pinfunction "LV_6") (pintype "bidirectional"))
    )
    (net (code "75") (name "unconnected-(U$3-OSC-Pad7)") (class "Default")
      (node (ref "U$3") (pin "7") (pinfunction "OSC_7") (pintype "bidirectional"))
    )
  )
)
